# Gate_Driver.net
KiCad netlist of a schematic drawn in Altium Designer
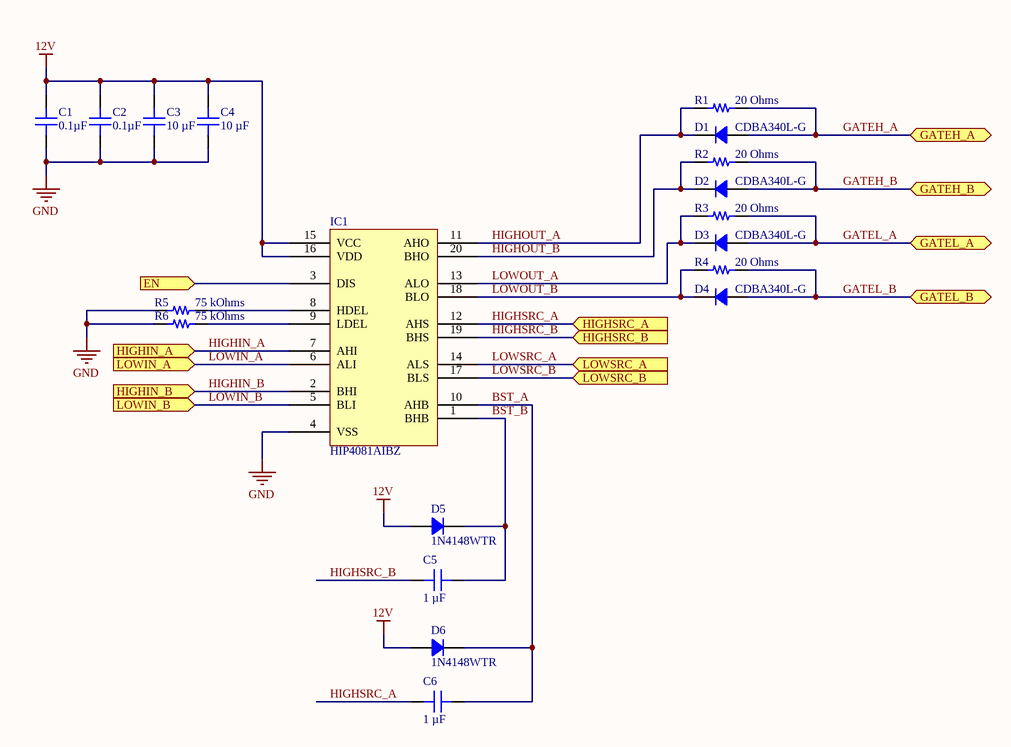
[diagram p0: Gate Driver.SchDoc]

(export (version "E")
  (design (tool "Eeschema 10.0.6"))
  (components
    (comp (ref "C1")
      (value "0.1µF")
      (footprint "CAP 0603_1608")
      (description "CAP CER 0.1UF 50V X7R 0603")
      (fields (field (name "PART NUMBER") "06035C104MAT2A") (field (name "MANUFACTURER") "AVX Corporation"))
      (libsource (lib "altiumlibrary.com") (part "Capacitor"))
    )
    (comp (ref "C2")
      (value "0.1µF")
      (footprint "CAP 0603_1608")
      (description "CAP CER 0.1UF 50V X7R 0603")
      (fields (field (name "PART NUMBER") "06035C104MAT2A") (field (name "MANUFACTURER") "AVX Corporation"))
      (libsource (lib "altiumlibrary.com") (part "Capacitor"))
    )
    (comp (ref "C3")
      (value "10 µF")
      (footprint "CAP 1206_3216 - 0.8MM")
      (description "CAP CER 10UF 50V X5R 1206")
      (fields
        (field (name "PART NUMBER") "GRT31CR61H106ME01L")
        (field (name "MANUFACTURER") "Murata Electronics")
      )
      (libsource (lib "altiumlibrary.com") (part "Capacitor"))
    )
    (comp (ref "C4")
      (value "10 µF")
      (footprint "CAP 1206_3216 - 0.8MM")
      (description "CAP CER 10UF 50V X5R 1206")
      (fields
        (field (name "PART NUMBER") "GRT31CR61H106ME01L")
        (field (name "MANUFACTURER") "Murata Electronics")
      )
      (libsource (lib "altiumlibrary.com") (part "Capacitor"))
    )
    (comp (ref "C5")
      (value "1 µF")
      (footprint "CAP 0805_2012")
      (description "CAP CER 1UF 50V X7R 0805")
      (fields (field (name "PART NUMBER") "08055C105KAZ2A") (field (name "MANUFACTURER") "KYOCERA AVX"))
      (libsource (lib "altiumlibrary.com") (part "Capacitor"))
    )
    (comp (ref "C6")
      (value "1 µF")
      (footprint "CAP 0805_2012")
      (description "CAP CER 1UF 50V X7R 0805")
      (fields (field (name "PART NUMBER") "08055C105KAZ2A") (field (name "MANUFACTURER") "KYOCERA AVX"))
      (libsource (lib "altiumlibrary.com") (part "Capacitor"))
    )
    (comp (ref "D1")
      (value "CDBA340L-G")
      (footprint "DO214AC SMA")
      (description "DIODE SCHOTTKY 40V 3A DO214AC")
      (fields (field (name "MANUFACTURER") "Comchip Technology"))
      (libsource (lib "altiumlibrary.com") (part "Diode"))
    )
    (comp (ref "D2")
      (value "CDBA340L-G")
      (footprint "DO214AC SMA")
      (description "DIODE SCHOTTKY 40V 3A DO214AC")
      (fields (field (name "MANUFACTURER") "Comchip Technology"))
      (libsource (lib "altiumlibrary.com") (part "Diode"))
    )
    (comp (ref "D3")
      (value "CDBA340L-G")
      (footprint "DO214AC SMA")
      (description "DIODE SCHOTTKY 40V 3A DO214AC")
      (fields (field (name "MANUFACTURER") "Comchip Technology"))
      (libsource (lib "altiumlibrary.com") (part "Diode"))
    )
    (comp (ref "D4")
      (value "CDBA340L-G")
      (footprint "DO214AC SMA")
      (description "DIODE SCHOTTKY 40V 3A DO214AC")
      (fields (field (name "MANUFACTURER") "Comchip Technology"))
      (libsource (lib "altiumlibrary.com") (part "Diode"))
    )
    (comp (ref "D5")
      (value "1N4148WTR")
      (footprint "SOD-123")
      (description "DIODE GEN PURP 75V 250MA SOD123")
      (fields (field (name "MANUFACTURER") "SMC Diode Solutions"))
      (libsource (lib "altiumlibrary.com") (part "Diode"))
    )
    (comp (ref "D6")
      (value "1N4148WTR")
      (footprint "SOD-123")
      (description "DIODE GEN PURP 75V 250MA SOD123")
      (fields (field (name "MANUFACTURER") "SMC Diode Solutions"))
      (libsource (lib "altiumlibrary.com") (part "Diode"))
    )
    (comp (ref "IC1")
      (value "HIP4081AIBZ")
      (footprint "INTERSIL SOIC-20 WIDE")
      (description "IC GATE DRVR HALF-BRIDGE 20SOIC")
      (fields (field (name "MANUFACTURER") "Renesas Electronics America Inc."))
      (libsource (lib "altiumlibrary.com") (part "Intersil HIP4081A"))
    )
    (comp (ref "R1")
      (value "20 Ohms")
      (footprint "RES 0805_2012")
      (description "RES SMD 20 OHM 5% 1/8W 0805")
      (fields
        (field (name "PART NUMBER") "ERJ-6GEYJ200V")
        (field (name "MANUFACTURER") "Panasonic Electronic Components")
      )
      (libsource (lib "altiumlibrary.com") (part "Resistor"))
    )
    (comp (ref "R2")
      (value "20 Ohms")
      (footprint "RES 0805_2012")
      (description "RES SMD 20 OHM 5% 1/8W 0805")
      (fields
        (field (name "PART NUMBER") "ERJ-6GEYJ200V")
        (field (name "MANUFACTURER") "Panasonic Electronic Components")
      )
      (libsource (lib "altiumlibrary.com") (part "Resistor"))
    )
    (comp (ref "R3")
      (value "20 Ohms")
      (footprint "RES 0805_2012")
      (description "RES SMD 20 OHM 5% 1/8W 0805")
      (fields
        (field (name "PART NUMBER") "ERJ-6GEYJ200V")
        (field (name "MANUFACTURER") "Panasonic Electronic Components")
      )
      (libsource (lib "altiumlibrary.com") (part "Resistor"))
    )
    (comp (ref "R4")
      (value "20 Ohms")
      (footprint "RES 0805_2012")
      (description "RES SMD 20 OHM 5% 1/8W 0805")
      (fields
        (field (name "PART NUMBER") "ERJ-6GEYJ200V")
        (field (name "MANUFACTURER") "Panasonic Electronic Components")
      )
      (libsource (lib "altiumlibrary.com") (part "Resistor"))
    )
    (comp (ref "R5")
      (value "75 kOhms")
      (footprint "RES 0603_1608")
      (description "RES 75K OHM 1% 1/10W 0603")
      (fields (field (name "PART NUMBER") "CRCW060375K0FKEAC") (field (name "MANUFACTURER") "Vishay Dale"))
      (libsource (lib "altiumlibrary.com") (part "Resistor"))
    )
    (comp (ref "R6")
      (value "75 kOhms")
      (footprint "RES 0603_1608")
      (description "RES 75K OHM 1% 1/10W 0603")
      (fields (field (name "PART NUMBER") "CRCW060375K0FKEAC") (field (name "MANUFACTURER") "Vishay Dale"))
      (libsource (lib "altiumlibrary.com") (part "Resistor"))
    )
  )
  (nets
    (net (code "1") (name "/BST_A") (class "Default")
      (node (ref "C6") (pin "2") (pinfunction "2_2") (pintype "passive"))
      (node (ref "D6") (pin "2") (pinfunction "2_2") (pintype "passive"))
      (node (ref "IC1") (pin "10") (pinfunction "AHB_10") (pintype "passive"))
    )
    (net (code "2") (name "/BST_B") (class "Default")
      (node (ref "C5") (pin "2") (pinfunction "2_2") (pintype "passive"))
      (node (ref "D5") (pin "2") (pinfunction "2_2") (pintype "passive"))
      (node (ref "IC1") (pin "1") (pinfunction "BHB_1") (pintype "passive"))
    )
    (net (code "3") (name "/EN") (class "Default")
      (node (ref "IC1") (pin "3") (pinfunction "DIS_3") (pintype "passive"))
    )
    (net (code "4") (name "/GATEH_A") (class "Default")
      (node (ref "D1") (pin "1") (pinfunction "1_1") (pintype "passive"))
      (node (ref "R1") (pin "2") (pinfunction "2_2") (pintype "passive"))
    )
    (net (code "5") (name "/GATEH_B") (class "Default")
      (node (ref "D2") (pin "1") (pinfunction "1_1") (pintype "passive"))
      (node (ref "R2") (pin "2") (pinfunction "2_2") (pintype "passive"))
    )
    (net (code "6") (name "/GATEL_A") (class "Default")
      (node (ref "D3") (pin "1") (pinfunction "1_1") (pintype "passive"))
      (node (ref "R3") (pin "2") (pinfunction "2_2") (pintype "passive"))
    )
    (net (code "7") (name "/GATEL_B") (class "Default")
      (node (ref "D4") (pin "1") (pinfunction "1_1") (pintype "passive"))
      (node (ref "R4") (pin "2") (pinfunction "2_2") (pintype "passive"))
    )
    (net (code "8") (name "/HIGHIN_A") (class "Default")
      (node (ref "IC1") (pin "7") (pinfunction "AHI_7") (pintype "passive"))
    )
    (net (code "9") (name "/HIGHIN_B") (class "Default")
      (node (ref "IC1") (pin "2") (pinfunction "BHI_2") (pintype "passive"))
    )
    (net (code "10") (name "/HIGHOUT_A") (class "Default")
      (node (ref "D1") (pin "2") (pinfunction "2_2") (pintype "passive"))
      (node (ref "IC1") (pin "11") (pinfunction "AHO_11") (pintype "passive"))
      (node (ref "R1") (pin "1") (pinfunction "1_1") (pintype "passive"))
    )
    (net (code "11") (name "/HIGHOUT_B") (class "Default")
      (node (ref "D2") (pin "2") (pinfunction "2_2") (pintype "passive"))
      (node (ref "IC1") (pin "20") (pinfunction "BHO_20") (pintype "passive"))
      (node (ref "R2") (pin "1") (pinfunction "1_1") (pintype "passive"))
    )
    (net (code "12") (name "/HIGHSRC_A") (class "Default")
      (node (ref "C6") (pin "1") (pinfunction "1_1") (pintype "passive"))
      (node (ref "IC1") (pin "12") (pinfunction "AHS_12") (pintype "passive"))
    )
    (net (code "13") (name "/HIGHSRC_B") (class "Default")
      (node (ref "C5") (pin "1") (pinfunction "1_1") (pintype "passive"))
      (node (ref "IC1") (pin "19") (pinfunction "BHS_19") (pintype "passive"))
    )
    (net (code "14") (name "/LOWIN_A") (class "Default")
      (node (ref "IC1") (pin "6") (pinfunction "ALI_6") (pintype "passive"))
    )
    (net (code "15") (name "/LOWIN_B") (class "Default")
      (node (ref "IC1") (pin "5") (pinfunction "BLI_5") (pintype "passive"))
    )
    (net (code "16") (name "/LOWOUT_A") (class "Default")
      (node (ref "D3") (pin "2") (pinfunction "2_2") (pintype "passive"))
      (node (ref "IC1") (pin "13") (pinfunction "ALO_13") (pintype "passive"))
      (node (ref "R3") (pin "1") (pinfunction "1_1") (pintype "passive"))
    )
    (net (code "17") (name "/LOWOUT_B") (class "Default")
      (node (ref "D4") (pin "2") (pinfunction "2_2") (pintype "passive"))
      (node (ref "IC1") (pin "18") (pinfunction "BLO_18") (pintype "passive"))
      (node (ref "R4") (pin "1") (pinfunction "1_1") (pintype "passive"))
    )
    (net (code "18") (name "/LOWSRC_A") (class "Default")
      (node (ref "IC1") (pin "14") (pinfunction "ALS_14") (pintype "passive"))
    )
    (net (code "19") (name "/LOWSRC_B") (class "Default")
      (node (ref "IC1") (pin "17") (pinfunction "BLS_17") (pintype "passive"))
    )
    (net (code "20") (name "12V") (class "Default")
      (node (ref "C1") (pin "2") (pinfunction "2_2") (pintype "passive"))
      (node (ref "C2") (pin "2") (pinfunction "2_2") (pintype "passive"))
      (node (ref "C3") (pin "2") (pinfunction "2_2") (pintype "passive"))
      (node (ref "C4") (pin "2") (pinfunction "2_2") (pintype "passive"))
      (node (ref "D5") (pin "1") (pinfunction "1_1") (pintype "passive"))
      (node (ref "D6") (pin "1") (pinfunction "1_1") (pintype "passive"))
      (node (ref "IC1") (pin "15") (pinfunction "VCC_15") (pintype "passive"))
      (node (ref "IC1") (pin "16") (pinfunction "VDD_16") (pintype "passive"))
    )
    (net (code "21") (name "GND") (class "Default")
      (node (ref "C1") (pin "1") (pinfunction "1_1") (pintype "passive"))
      (node (ref "C2") (pin "1") (pinfunction "1_1") (pintype "passive"))
      (node (ref "C3") (pin "1") (pinfunction "1_1") (pintype "passive"))
      (node (ref "C4") (pin "1") (pinfunction "1_1") (pintype "passive"))
      (node (ref "IC1") (pin "4") (pinfunction "VSS_4") (pintype "passive"))
      (node (ref "R5") (pin "1") (pinfunction "1_1") (pintype "passive"))
      (node (ref "R6") (pin "1") (pinfunction "1_1") (pintype "passive"))
    )
    (net (code "22") (name "Net-(IC1-HDEL)") (class "Default")
      (node (ref "IC1") (pin "8") (pinfunction "HDEL_8") (pintype "passive"))
      (node (ref "R5") (pin "2") (pinfunction "2_2") (pintype "passive"))
    )
    (net (code "23") (name "Net-(IC1-LDEL)") (class "Default")
      (node (ref "IC1") (pin "9") (pinfunction "LDEL_9") (pintype "passive"))
      (node (ref "R6") (pin "2") (pinfunction "2_2") (pintype "passive"))
    )
  )
)
